# pc_healthypi_move_nRF5340_v1.net
KiCad netlist of a schematic drawn in EAGLE
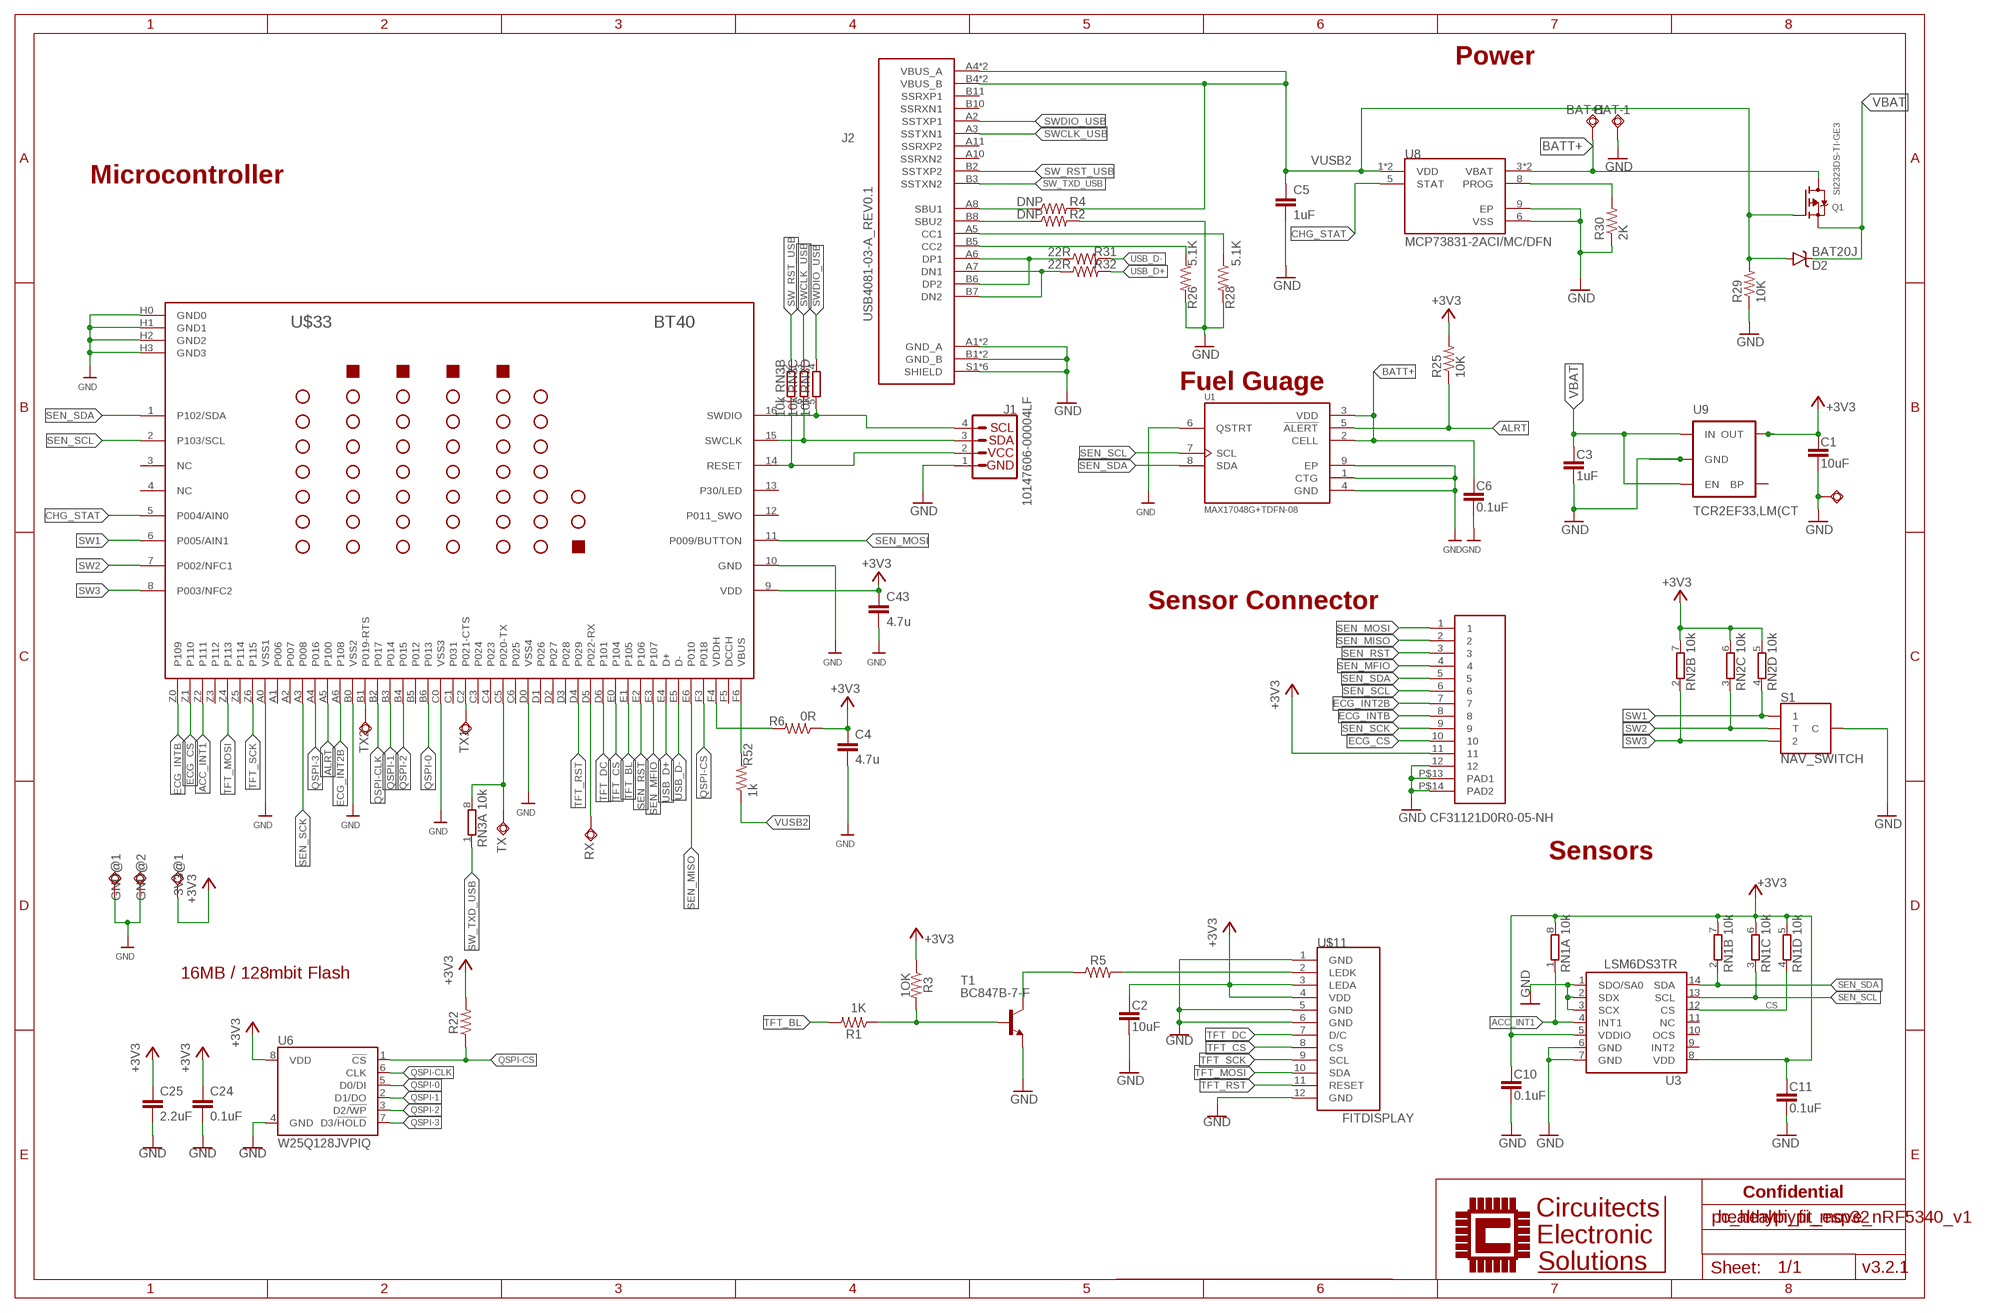
[diagram p0: schematic, sheet 1]

(export (version "E")
  (design (tool "Eeschema 10.0.6"))
  (components
    (comp (ref "3V3@1")
      (value "TPSQTP13SQ")
      (footprint "eagle-import:TP13SQ")
      (libsource (lib "eagle-import") (part "TPSQTP13SQ"))
    )
    (comp (ref "BAT+1")
      (value "TPSQTP13SQ")
      (footprint "eagle-import:TP13SQ")
      (libsource (lib "eagle-import") (part "TPSQTP13SQ"))
    )
    (comp (ref "BAT-1")
      (value "TPSQTP13SQ")
      (footprint "eagle-import:TP13SQ")
      (libsource (lib "eagle-import") (part "TPSQTP13SQ"))
    )
    (comp (ref "C1")
      (value "10uF")
      (footprint "eagle-import:0603@1")
      (libsource (lib "eagle-import") (part "0.1UF-0603-100V-10%"))
    )
    (comp (ref "C2")
      (value "10uF")
      (footprint "eagle-import:0603@1")
      (libsource (lib "eagle-import") (part "0.1UF-0603-100V-10%"))
    )
    (comp (ref "C3")
      (value "1uF")
      (footprint "eagle-import:0402-TIGHT")
      (libsource (lib "eagle-import") (part "0.1UF-0402T-6.3V-10%-X7R"))
    )
    (comp (ref "C4")
      (value "4.7u")
      (footprint "eagle-import:C0402")
      (libsource (lib "eagle-import") (part "C-EUC0402"))
    )
    (comp (ref "C5")
      (value "1uF")
      (footprint "eagle-import:0402-TIGHT")
      (libsource (lib "eagle-import") (part "2.2UF-0402_TIGHT-10V-10%-X5R"))
    )
    (comp (ref "C6")
      (value "0.1uF")
      (footprint "eagle-import:0402-TIGHT")
      (libsource (lib "eagle-import") (part "0.1UF-0402T-6.3V-10%-X7R"))
    )
    (comp (ref "C10")
      (value "0.1uF")
      (footprint "eagle-import:0402-TIGHT")
      (libsource (lib "eagle-import") (part "0.1UF-0402T-6.3V-10%-X7R"))
    )
    (comp (ref "C11")
      (value "0.1uF")
      (footprint "eagle-import:0402-TIGHT")
      (libsource (lib "eagle-import") (part "0.1UF-0402T-6.3V-10%-X7R"))
    )
    (comp (ref "C24")
      (value "0.1uF")
      (footprint "eagle-import:0402-TIGHT")
      (libsource (lib "eagle-import") (part "0.1UF-0402T-6.3V-10%-X7R"))
    )
    (comp (ref "C25")
      (value "2.2uF")
      (footprint "eagle-import:0402-TIGHT")
      (libsource (lib "eagle-import") (part "2.2UF-0402_TIGHT-10V-10%-X5R"))
    )
    (comp (ref "C43")
      (value "4.7u")
      (footprint "eagle-import:C0402")
      (libsource (lib "eagle-import") (part "C-EUC0402"))
    )
    (comp (ref "D2")
      (value "BAT20J")
      (footprint "eagle-import:SOD-323")
      (libsource (lib "eagle-import") (part "DIODE-SCHOTTKY-BAT20J"))
    )
    (comp (ref "GND@1")
      (value "TPSQTP13SQ")
      (footprint "eagle-import:TP13SQ")
      (libsource (lib "eagle-import") (part "TPSQTP13SQ"))
    )
    (comp (ref "GND@2")
      (value "TPSQTP13SQ")
      (footprint "eagle-import:TP13SQ")
      (libsource (lib "eagle-import") (part "TPSQTP13SQ"))
    )
    (comp (ref "J1")
      (value "10147606-00004LF")
      (footprint "eagle-import:JST04_1MM_RA")
      (libsource (lib "eagle-import") (part "QWIIC_CONNECTORJS-1MM"))
    )
    (comp (ref "J2")
      (value "USB4081-03-A_REV0.1")
      (footprint "eagle-import:GCT_USB4081-03-A_REV0.1")
      (fields (field (name "MF") "Global Connector Technology") (field (name "MP") "USB4081-03-A"))
      (libsource (lib "eagle-import") (part "USB4081-03-A_REV0.1"))
    )
    (comp (ref "Q1")
      (value "SI2323DS-TI-GE3")
      (footprint "eagle-import:SOT23-R")
      (libsource (lib "eagle-import") (part "MOSFET-P"))
    )
    (comp (ref "R1")
      (value "200")
      (footprint "eagle-import:R0402")
      (libsource (lib "eagle-import") (part "R-US_R0402"))
    )
    (comp (ref "R2")
      (value "DNP")
      (footprint "eagle-import:0402-RES")
      (libsource (lib "eagle-import") (part "RESISTOR0402-RES"))
    )
    (comp (ref "R3")
      (value "200")
      (footprint "eagle-import:R0402")
      (libsource (lib "eagle-import") (part "R-US_R0402"))
    )
    (comp (ref "R4")
      (value "DNP")
      (footprint "eagle-import:0402-RES")
      (libsource (lib "eagle-import") (part "RESISTOR0402-RES"))
    )
    (comp (ref "R5")
      (value "200R")
      (footprint "eagle-import:R0402")
      (libsource (lib "eagle-import") (part "R-US_R0402"))
    )
    (comp (ref "R6")
      (value "0R")
      (footprint "eagle-import:0402-RES")
      (libsource (lib "eagle-import") (part "RESISTOR0402-RES"))
    )
    (comp (ref "R22")
      (value "10k")
      (footprint "eagle-import:R0402")
      (libsource (lib "eagle-import") (part "R-US_R0402"))
    )
    (comp (ref "R25")
      (value "10K")
      (footprint "eagle-import:0402-RES")
      (libsource (lib "eagle-import") (part "RESISTOR0402-RES"))
    )
    (comp (ref "R26")
      (value "5.1K")
      (footprint "eagle-import:0402-RES")
      (libsource (lib "eagle-import") (part "RESISTOR0402-RES"))
    )
    (comp (ref "R28")
      (value "5.1K")
      (footprint "eagle-import:0402-RES")
      (libsource (lib "eagle-import") (part "RESISTOR0402-RES"))
    )
    (comp (ref "R29")
      (value "10K")
      (footprint "eagle-import:R0402")
      (libsource (lib "eagle-import") (part "R-US_R0402"))
    )
    (comp (ref "R30")
      (value "2K")
      (footprint "eagle-import:R0402")
      (libsource (lib "eagle-import") (part "R-US_R0402"))
    )
    (comp (ref "R31")
      (value "22R")
      (footprint "eagle-import:0402-RES")
      (libsource (lib "eagle-import") (part "RESISTOR0402-RES"))
    )
    (comp (ref "R32")
      (value "22R")
      (footprint "eagle-import:0402-RES")
      (libsource (lib "eagle-import") (part "RESISTOR0402-RES"))
    )
    (comp (ref "R52")
      (value "1k")
      (footprint "eagle-import:0402-RES")
      (libsource (lib "eagle-import") (part "RESISTOR0402-RES"))
    )
    (comp (ref "RN1")
      (value "10k")
      (footprint "eagle-import:4X0402ARV341")
      (libsource (lib "eagle-import") (part "4R-N0402ARV341"))
    )
    (comp (ref "RN2")
      (value "10k")
      (footprint "eagle-import:4X0402ARV341")
      (libsource (lib "eagle-import") (part "4R-N0402ARV341"))
    )
    (comp (ref "RN3")
      (value "10k")
      (footprint "eagle-import:4X0402ARV341")
      (libsource (lib "eagle-import") (part "4R-N0402ARV341"))
    )
    (comp (ref "RX")
      (value "TPSQTP13SQ")
      (footprint "eagle-import:TP13SQ")
      (libsource (lib "eagle-import") (part "TPSQTP13SQ"))
    )
    (comp (ref "S1")
      (value "NAV_SWITCH")
      (footprint "eagle-import:NAV_SWITCH")
      (libsource (lib "eagle-import") (part "NAV_SWITCH"))
    )
    (comp (ref "SWIO6")
      (value "TPSQTP11R")
      (footprint "eagle-import:TP11R")
      (libsource (lib "eagle-import") (part "TPSQTP11R"))
    )
    (comp (ref "T1")
      (value "BC847B-7-F")
      (footprint "eagle-import:SOT23-BEC")
      (libsource (lib "eagle-import") (part "-NPN-SOT23-BECMMBT2222ALT1"))
    )
    (comp (ref "TX")
      (value "TPSQTP13SQ")
      (footprint "eagle-import:TP13SQ")
      (libsource (lib "eagle-import") (part "TPSQTP13SQ"))
    )
    (comp (ref "TX1")
      (value "TPSQTP13SQ")
      (footprint "eagle-import:TP13SQ")
      (libsource (lib "eagle-import") (part "TPSQTP13SQ"))
    )
    (comp (ref "TX2")
      (value "TPSQTP13SQ")
      (footprint "eagle-import:TP13SQ")
      (libsource (lib "eagle-import") (part "TPSQTP13SQ"))
    )
    (comp (ref "U$5")
      (value "CF31121D0R0-05-NH")
      (footprint "eagle-import:CF31121D0R0-05-NH")
      (libsource (lib "eagle-import") (part "CF31121D0R0-05-NH"))
    )
    (comp (ref "U$11")
      (value "FITDISPLAY")
      (footprint "eagle-import:FITDISPLAY")
      (libsource (lib "eagle-import") (part "FITDISPLAY"))
    )
    (comp (ref "U$33")
      (value "BT40")
      (footprint "eagle-import:BT40")
      (libsource (lib "eagle-import") (part "BT40"))
    )
    (comp (ref "U1")
      (value "MAX17048G+TDFN-08")
      (footprint "eagle-import:SON50P200X200X80-9N")
      (fields (field (name "MF") "Analog Devices") (field (name "MP") "MAX17048G+"))
      (libsource (lib "eagle-import") (part "MAX17048G+TDFN-08"))
    )
    (comp (ref "U3")
      (value "LSM6DS3TR")
      (footprint "eagle-import:LGA14L")
      (libsource (lib "eagle-import") (part "LSM6DS3"))
    )
    (comp (ref "U6")
      (value "W25Q128JVPIQ")
      (footprint "eagle-import:WSON-8-6X5-SKINNY_CENTERPAD")
      (libsource (lib "eagle-import") (part "W25QXX128MBIT-6X5-SKINNY_CENTER"))
    )
    (comp (ref "U8")
      (value "MCP73831-2ACI/MC/DFN")
      (footprint "eagle-import:SON50P200X300X100-9N")
      (fields (field (name "MF") "Microchip Technology") (field (name "MP") "MCP73831-2ACI/MC"))
      (libsource (lib "eagle-import") (part "MCP73831-2ACI/MC/DFN"))
    )
    (comp (ref "U9")
      (value "TCR2EF33,LM(CT")
      (footprint "eagle-import:SOT23-5")
      (libsource (lib "eagle-import") (part "V_REG_LDOSMD"))
    )
  )
  (nets
    (net (code "1") (name "+3V3") (class "Default")
      (node (ref "3V3@1") (pin "TP") (pinfunction "TP_TP") (pintype "input"))
      (node (ref "C1") (pin "1") (pinfunction "1_1") (pintype "passive"))
      (node (ref "C10") (pin "1") (pinfunction "1_1") (pintype "passive"))
      (node (ref "C11") (pin "1") (pinfunction "1_1") (pintype "passive"))
      (node (ref "C2") (pin "1") (pinfunction "1_1") (pintype "passive"))
      (node (ref "C24") (pin "1") (pinfunction "1_1") (pintype "passive"))
      (node (ref "C25") (pin "1") (pinfunction "1_1") (pintype "passive"))
      (node (ref "C4") (pin "1") (pinfunction "1_1") (pintype "passive"))
      (node (ref "C43") (pin "1") (pinfunction "1_1") (pintype "passive"))
      (node (ref "R22") (pin "2") (pinfunction "2_2") (pintype "passive"))
      (node (ref "R25") (pin "2") (pinfunction "2_2") (pintype "passive"))
      (node (ref "R3") (pin "1") (pinfunction "1_1") (pintype "passive"))
      (node (ref "R6") (pin "1") (pinfunction "1_1") (pintype "passive"))
      (node (ref "RN1") (pin "5") (pinfunction "2_5") (pintype "passive"))
      (node (ref "RN1") (pin "6") (pinfunction "2_6") (pintype "passive"))
      (node (ref "RN1") (pin "7") (pinfunction "2_7") (pintype "passive"))
      (node (ref "RN1") (pin "8") (pinfunction "2_8") (pintype "passive"))
      (node (ref "RN2") (pin "5") (pinfunction "2_5") (pintype "passive"))
      (node (ref "RN2") (pin "6") (pinfunction "2_6") (pintype "passive"))
      (node (ref "RN2") (pin "7") (pinfunction "2_7") (pintype "passive"))
      (node (ref "U$11") (pin "3") (pinfunction "LEDA_3") (pintype "bidirectional"))
      (node (ref "U$11") (pin "4") (pinfunction "VDD_4") (pintype "bidirectional"))
      (node (ref "U$33") (pin "9") (pinfunction "VDD_9") (pintype "bidirectional"))
      (node (ref "U$5") (pin "11") (pinfunction "11_11") (pintype "bidirectional"))
      (node (ref "U3") (pin "5") (pinfunction "VDDIO_5") (pintype "bidirectional"))
      (node (ref "U3") (pin "8") (pinfunction "VDD_8") (pintype "bidirectional"))
      (node (ref "U6") (pin "8") (pinfunction "VDD_8") (pintype "bidirectional"))
      (node (ref "U9") (pin "5") (pinfunction "OUT_5") (pintype "passive"))
    )
    (net (code "2") (name "/CS") (class "Default")
      (node (ref "RN1") (pin "4") (pinfunction "1_4") (pintype "passive"))
      (node (ref "U3") (pin "12") (pinfunction "CS_12") (pintype "bidirectional"))
    )
    (net (code "3") (name "ACC_INT1") (class "Default")
      (node (ref "RN1") (pin "1") (pinfunction "1_1") (pintype "passive"))
      (node (ref "U$33") (pin "Z2") (pinfunction "P111_Z2") (pintype "bidirectional"))
      (node (ref "U3") (pin "4") (pinfunction "INT1_4") (pintype "bidirectional"))
    )
    (net (code "4") (name "ALRT") (class "Default")
      (node (ref "R25") (pin "1") (pinfunction "1_1") (pintype "passive"))
      (node (ref "U$33") (pin "A5") (pinfunction "P100_A5") (pintype "bidirectional"))
      (node (ref "U1") (pin "5") (pinfunction "~{ALERT}_5") (pintype "output"))
    )
    (net (code "5") (name "BATT+") (class "Default")
      (node (ref "BAT+1") (pin "TP") (pinfunction "TP_TP") (pintype "input"))
      (node (ref "C6") (pin "1") (pinfunction "1_1") (pintype "passive"))
      (node (ref "Q1") (pin "3") (pinfunction "D_3") (pintype "passive"))
      (node (ref "U1") (pin "2") (pinfunction "CELL_2") (pintype "power_in"))
      (node (ref "U1") (pin "3") (pinfunction "VDD_3") (pintype "power_in"))
      (node (ref "U8") (pin "3") (pinfunction "VBAT_3") (pintype "output"))
      (node (ref "U8") (pin "4") (pinfunction "VBAT_4") (pintype "output"))
    )
    (net (code "6") (name "CHG_STAT") (class "Default")
      (node (ref "U$33") (pin "5") (pinfunction "P004/AIN0_5") (pintype "bidirectional"))
      (node (ref "U8") (pin "5") (pinfunction "STAT_5") (pintype "output"))
    )
    (net (code "7") (name "ECG_CS") (class "Default")
      (node (ref "U$33") (pin "Z1") (pinfunction "P110_Z1") (pintype "bidirectional"))
      (node (ref "U$5") (pin "10") (pinfunction "10_10") (pintype "bidirectional"))
    )
    (net (code "8") (name "ECG_INT2B") (class "Default")
      (node (ref "U$33") (pin "A6") (pinfunction "P108_A6") (pintype "bidirectional"))
      (node (ref "U$5") (pin "7") (pinfunction "7_7") (pintype "bidirectional"))
    )
    (net (code "9") (name "ECG_INTB") (class "Default")
      (node (ref "U$33") (pin "Z0") (pinfunction "P109_Z0") (pintype "bidirectional"))
      (node (ref "U$5") (pin "8") (pinfunction "8_8") (pintype "bidirectional"))
    )
    (net (code "10") (name "GND") (class "Default")
      (node (ref "BAT-1") (pin "TP") (pinfunction "TP_TP") (pintype "input"))
      (node (ref "C1") (pin "2") (pinfunction "2_2") (pintype "passive"))
      (node (ref "C10") (pin "2") (pinfunction "2_2") (pintype "passive"))
      (node (ref "C11") (pin "2") (pinfunction "2_2") (pintype "passive"))
      (node (ref "C2") (pin "2") (pinfunction "2_2") (pintype "passive"))
      (node (ref "C24") (pin "2") (pinfunction "2_2") (pintype "passive"))
      (node (ref "C25") (pin "2") (pinfunction "2_2") (pintype "passive"))
      (node (ref "C3") (pin "2") (pinfunction "2_2") (pintype "passive"))
      (node (ref "C4") (pin "2") (pinfunction "2_2") (pintype "passive"))
      (node (ref "C43") (pin "2") (pinfunction "2_2") (pintype "passive"))
      (node (ref "C5") (pin "2") (pinfunction "2_2") (pintype "passive"))
      (node (ref "C6") (pin "2") (pinfunction "2_2") (pintype "passive"))
      (node (ref "GND@1") (pin "TP") (pinfunction "TP_TP") (pintype "input"))
      (node (ref "GND@2") (pin "TP") (pinfunction "TP_TP") (pintype "input"))
      (node (ref "J1") (pin "1") (pinfunction "1_1") (pintype "power_in"))
      (node (ref "J2") (pin "A1") (pinfunction "GND_A_A1") (pintype "power_in"))
      (node (ref "J2") (pin "A12") (pinfunction "GND_A_A12") (pintype "power_in"))
      (node (ref "J2") (pin "B1") (pinfunction "GND_B_B1") (pintype "power_in"))
      (node (ref "J2") (pin "B12") (pinfunction "GND_B_B12") (pintype "power_in"))
      (node (ref "J2") (pin "S1") (pinfunction "SHIELD_S1") (pintype "passive"))
      (node (ref "J2") (pin "S2") (pinfunction "SHIELD_S2") (pintype "passive"))
      (node (ref "J2") (pin "S3") (pinfunction "SHIELD_S3") (pintype "passive"))
      (node (ref "J2") (pin "S4") (pinfunction "SHIELD_S4") (pintype "passive"))
      (node (ref "J2") (pin "S5") (pinfunction "SHIELD_S5") (pintype "passive"))
      (node (ref "J2") (pin "S6") (pinfunction "SHIELD_S6") (pintype "passive"))
      (node (ref "R2") (pin "2") (pinfunction "2_2") (pintype "passive"))
      (node (ref "R26") (pin "2") (pinfunction "2_2") (pintype "passive"))
      (node (ref "R28") (pin "2") (pinfunction "2_2") (pintype "passive"))
      (node (ref "R29") (pin "1") (pinfunction "1_1") (pintype "passive"))
      (node (ref "R30") (pin "1") (pinfunction "1_1") (pintype "passive"))
      (node (ref "S1") (pin "C") (pinfunction "C_C") (pintype "power_in"))
      (node (ref "SWIO6") (pin "TP") (pinfunction "TP_TP") (pintype "input"))
      (node (ref "T1") (pin "E") (pinfunction "E_E") (pintype "passive"))
      (node (ref "U$11") (pin "1") (pinfunction "GND_1") (pintype "bidirectional"))
      (node (ref "U$11") (pin "12") (pinfunction "GND_12") (pintype "bidirectional"))
      (node (ref "U$11") (pin "5") (pinfunction "GND_5") (pintype "bidirectional"))
      (node (ref "U$11") (pin "6") (pinfunction "GND_6") (pintype "bidirectional"))
      (node (ref "U$33") (pin "10") (pinfunction "GND_10") (pintype "bidirectional"))
      (node (ref "U$33") (pin "A0") (pinfunction "VSS1_A0") (pintype "bidirectional"))
      (node (ref "U$33") (pin "B0") (pinfunction "VSS2_B0") (pintype "bidirectional"))
      (node (ref "U$33") (pin "C0") (pinfunction "VSS3_C0") (pintype "bidirectional"))
      (node (ref "U$33") (pin "D0") (pinfunction "VSS4_D0") (pintype "bidirectional"))
      (node (ref "U$33") (pin "H0") (pinfunction "GND0_H0") (pintype "bidirectional"))
      (node (ref "U$33") (pin "H1") (pinfunction "GND1_H1") (pintype "bidirectional"))
      (node (ref "U$33") (pin "H2") (pinfunction "GND2_H2") (pintype "bidirectional"))
      (node (ref "U$33") (pin "H3") (pinfunction "GND3_H3") (pintype "bidirectional"))
      (node (ref "U$5") (pin "12") (pinfunction "12_12") (pintype "bidirectional"))
      (node (ref "U$5") (pin "P$13") (pinfunction "PAD1_P$13") (pintype "bidirectional"))
      (node (ref "U$5") (pin "P$14") (pinfunction "PAD2_P$14") (pintype "bidirectional"))
      (node (ref "U1") (pin "1") (pinfunction "CTG_1") (pintype "power_in"))
      (node (ref "U1") (pin "4") (pinfunction "GND_4") (pintype "power_in"))
      (node (ref "U1") (pin "6") (pinfunction "QSTRT_6") (pintype "input"))
      (node (ref "U1") (pin "9") (pinfunction "EP_9") (pintype "power_in"))
      (node (ref "U3") (pin "1") (pinfunction "SDO/SA0_1") (pintype "bidirectional"))
      (node (ref "U3") (pin "2") (pinfunction "SDX_2") (pintype "bidirectional"))
      (node (ref "U3") (pin "3") (pinfunction "SCX_3") (pintype "bidirectional"))
      (node (ref "U3") (pin "6") (pinfunction "GND_6") (pintype "bidirectional"))
      (node (ref "U3") (pin "7") (pinfunction "GND_7") (pintype "bidirectional"))
      (node (ref "U6") (pin "4") (pinfunction "GND_4") (pintype "bidirectional"))
      (node (ref "U8") (pin "6") (pinfunction "VSS_6") (pintype "power_in"))
      (node (ref "U8") (pin "9") (pinfunction "EP_9") (pintype "power_in"))
      (node (ref "U9") (pin "2") (pinfunction "GND_2") (pintype "input"))
    )
    (net (code "11") (name "Net-(J2-CC1)") (class "Default")
      (node (ref "J2") (pin "A5") (pinfunction "CC1_A5") (pintype "bidirectional"))
      (node (ref "R28") (pin "1") (pinfunction "1_1") (pintype "passive"))
    )
    (net (code "12") (name "Net-(J2-CC2)") (class "Default")
      (node (ref "J2") (pin "B5") (pinfunction "CC2_B5") (pintype "bidirectional"))
      (node (ref "R26") (pin "1") (pinfunction "1_1") (pintype "passive"))
    )
    (net (code "13") (name "Net-(J2-DN1)") (class "Default")
      (node (ref "J2") (pin "A7") (pinfunction "DN1_A7") (pintype "bidirectional"))
      (node (ref "J2") (pin "B7") (pinfunction "DN2_B7") (pintype "bidirectional"))
      (node (ref "R32") (pin "1") (pinfunction "1_1") (pintype "passive"))
    )
    (net (code "14") (name "Net-(J2-DP1)") (class "Default")
      (node (ref "J2") (pin "A6") (pinfunction "DP1_A6") (pintype "bidirectional"))
      (node (ref "J2") (pin "B6") (pinfunction "DP2_B6") (pintype "bidirectional"))
      (node (ref "R31") (pin "1") (pinfunction "1_1") (pintype "passive"))
    )
    (net (code "15") (name "Net-(J2-SBU1)") (class "Default")
      (node (ref "J2") (pin "A8") (pinfunction "SBU1_A8") (pintype "bidirectional"))
      (node (ref "R4") (pin "1") (pinfunction "1_1") (pintype "passive"))
    )
    (net (code "16") (name "Net-(J2-SBU2)") (class "Default")
      (node (ref "J2") (pin "B8") (pinfunction "SBU2_B8") (pintype "bidirectional"))
      (node (ref "R2") (pin "1") (pinfunction "1_1") (pintype "passive"))
    )
    (net (code "17") (name "Net-(R1-Pad1)") (class "Default")
      (node (ref "R1") (pin "1") (pinfunction "1_1") (pintype "passive"))
      (node (ref "R3") (pin "2") (pinfunction "2_2") (pintype "passive"))
      (node (ref "T1") (pin "B") (pinfunction "B_B") (pintype "passive"))
    )
    (net (code "18") (name "Net-(R5-Pad1)") (class "Default")
      (node (ref "R5") (pin "1") (pinfunction "1_1") (pintype "passive"))
      (node (ref "T1") (pin "C") (pinfunction "C_C") (pintype "passive"))
    )
    (net (code "19") (name "Net-(RN3A-2)") (class "Default")
      (node (ref "RN3") (pin "8") (pinfunction "2_8") (pintype "passive"))
      (node (ref "TX") (pin "TP") (pinfunction "TP_TP") (pintype "input"))
      (node (ref "U$33") (pin "C5") (pinfunction "P020-TX_C5") (pintype "bidirectional"))
    )
    (net (code "20") (name "Net-(RN3B-2)") (class "Default")
      (node (ref "J1") (pin "2") (pinfunction "2_2") (pintype "power_in"))
      (node (ref "RN3") (pin "7") (pinfunction "2_7") (pintype "passive"))
      (node (ref "U$33") (pin "14") (pinfunction "RESET_14") (pintype "bidirectional"))
    )
    (net (code "21") (name "Net-(RN3C-2)") (class "Default")
      (node (ref "J1") (pin "3") (pinfunction "3_3") (pintype "passive"))
      (node (ref "RN3") (pin "6") (pinfunction "2_6") (pintype "passive"))
      (node (ref "U$33") (pin "15") (pinfunction "SWCLK_15") (pintype "bidirectional"))
    )
    (net (code "22") (name "Net-(RN3D-2)") (class "Default")
      (node (ref "J1") (pin "4") (pinfunction "4_4") (pintype "passive"))
      (node (ref "RN3") (pin "5") (pinfunction "2_5") (pintype "passive"))
      (node (ref "U$33") (pin "16") (pinfunction "SWDIO_16") (pintype "bidirectional"))
    )
    (net (code "23") (name "Net-(U$11-LEDK)") (class "Default")
      (node (ref "R5") (pin "2") (pinfunction "2_2") (pintype "passive"))
      (node (ref "U$11") (pin "2") (pinfunction "LEDK_2") (pintype "bidirectional"))
    )
    (net (code "24") (name "Net-(U$33-P019-RTS)") (class "Default")
      (node (ref "TX2") (pin "TP") (pinfunction "TP_TP") (pintype "input"))
      (node (ref "U$33") (pin "B1") (pinfunction "P019-RTS_B1") (pintype "bidirectional"))
    )
    (net (code "25") (name "Net-(U$33-P021-CTS)") (class "Default")
      (node (ref "TX1") (pin "TP") (pinfunction "TP_TP") (pintype "input"))
      (node (ref "U$33") (pin "C2") (pinfunction "P021-CTS_C2") (pintype "bidirectional"))
    )
    (net (code "26") (name "Net-(U$33-P022-RX)") (class "Default")
      (node (ref "RX") (pin "TP") (pinfunction "TP_TP") (pintype "input"))
      (node (ref "U$33") (pin "D5") (pinfunction "P022-RX_D5") (pintype "bidirectional"))
    )
    (net (code "27") (name "Net-(U$33-VBUS)") (class "Default")
      (node (ref "R52") (pin "2") (pinfunction "2_2") (pintype "passive"))
      (node (ref "U$33") (pin "F6") (pinfunction "VBUS_F6") (pintype "bidirectional"))
    )
    (net (code "28") (name "Net-(U$33-VDDH)") (class "Default")
      (node (ref "R6") (pin "2") (pinfunction "2_2") (pintype "passive"))
      (node (ref "U$33") (pin "F4") (pinfunction "VDDH_F4") (pintype "bidirectional"))
    )
    (net (code "29") (name "Net-(U8-PROG)") (class "Default")
      (node (ref "R30") (pin "2") (pinfunction "2_2") (pintype "passive"))
      (node (ref "U8") (pin "8") (pinfunction "PROG_8") (pintype "input"))
    )
    (net (code "30") (name "QSPI-0") (class "Default")
      (node (ref "U$33") (pin "B6") (pinfunction "P013_B6") (pintype "bidirectional"))
      (node (ref "U6") (pin "5") (pinfunction "D0/DI_5") (pintype "bidirectional"))
    )
    (net (code "31") (name "QSPI-1") (class "Default")
      (node (ref "U$33") (pin "B3") (pinfunction "P014_B3") (pintype "bidirectional"))
      (node (ref "U6") (pin "2") (pinfunction "D1/DO_2") (pintype "bidirectional"))
    )
    (net (code "32") (name "QSPI-2") (class "Default")
      (node (ref "U$33") (pin "B4") (pinfunction "P015_B4") (pintype "bidirectional"))
      (node (ref "U6") (pin "3") (pinfunction "D2/~{WP}_3") (pintype "bidirectional"))
    )
    (net (code "33") (name "QSPI-3") (class "Default")
      (node (ref "U$33") (pin "A4") (pinfunction "P016_A4") (pintype "bidirectional"))
      (node (ref "U6") (pin "7") (pinfunction "D3/~{HOLD}_7") (pintype "bidirectional"))
    )
    (net (code "34") (name "QSPI-CLK") (class "Default")
      (node (ref "U$33") (pin "B2") (pinfunction "P017_B2") (pintype "bidirectional"))
      (node (ref "U6") (pin "6") (pinfunction "CLK_6") (pintype "bidirectional"))
    )
    (net (code "35") (name "QSPI-CS") (class "Default")
      (node (ref "R22") (pin "1") (pinfunction "1_1") (pintype "passive"))
      (node (ref "U$33") (pin "F3") (pinfunction "P018_F3") (pintype "bidirectional"))
      (node (ref "U6") (pin "1") (pinfunction "~{CS}_1") (pintype "bidirectional"))
    )
    (net (code "36") (name "SEN_MFIO") (class "Default")
      (node (ref "U$33") (pin "E3") (pinfunction "P107_E3") (pintype "bidirectional"))
      (node (ref "U$5") (pin "4") (pinfunction "4_4") (pintype "bidirectional"))
    )
    (net (code "37") (name "SEN_MISO") (class "Default")
      (node (ref "U$33") (pin "E6") (pinfunction "P010_E6") (pintype "bidirectional"))
      (node (ref "U$5") (pin "2") (pinfunction "2_2") (pintype "bidirectional"))
    )
    (net (code "38") (name "SEN_MOSI") (class "Default")
      (node (ref "U$33") (pin "11") (pinfunction "P009/BUTTON_11") (pintype "bidirectional"))
      (node (ref "U$5") (pin "1") (pinfunction "1_1") (pintype "bidirectional"))
    )
    (net (code "39") (name "SEN_RST") (class "Default")
      (node (ref "U$33") (pin "E2") (pinfunction "P106_E2") (pintype "bidirectional"))
      (node (ref "U$5") (pin "3") (pinfunction "3_3") (pintype "bidirectional"))
    )
    (net (code "40") (name "SEN_SCK") (class "Default")
      (node (ref "U$33") (pin "A3") (pinfunction "P008_A3") (pintype "bidirectional"))
      (node (ref "U$5") (pin "9") (pinfunction "9_9") (pintype "bidirectional"))
    )
    (net (code "41") (name "SEN_SCL") (class "Default")
      (node (ref "RN1") (pin "3") (pinfunction "1_3") (pintype "passive"))
      (node (ref "U$33") (pin "2") (pinfunction "P103/SCL_2") (pintype "bidirectional"))
      (node (ref "U$5") (pin "6") (pinfunction "6_6") (pintype "bidirectional"))
      (node (ref "U1") (pin "7") (pinfunction "SCL_7") (pintype "input"))
      (node (ref "U3") (pin "13") (pinfunction "SCL_13") (pintype "bidirectional"))
    )
    (net (code "42") (name "SEN_SDA") (class "Default")
      (node (ref "RN1") (pin "2") (pinfunction "1_2") (pintype "passive"))
      (node (ref "U$33") (pin "1") (pinfunction "P102/SDA_1") (pintype "bidirectional"))
      (node (ref "U$5") (pin "5") (pinfunction "5_5") (pintype "bidirectional"))
      (node (ref "U1") (pin "8") (pinfunction "SDA_8") (pintype "bidirectional"))
      (node (ref "U3") (pin "14") (pinfunction "SDA_14") (pintype "bidirectional"))
    )
    (net (code "43") (name "SW1") (class "Default")
      (node (ref "RN2") (pin "4") (pinfunction "1_4") (pintype "passive"))
      (node (ref "S1") (pin "1") (pinfunction "1_1") (pintype "input"))
      (node (ref "U$33") (pin "6") (pinfunction "P005/AIN1_6") (pintype "bidirectional"))
    )
    (net (code "44") (name "SW2") (class "Default")
      (node (ref "RN2") (pin "3") (pinfunction "1_3") (pintype "passive"))
      (node (ref "S1") (pin "T") (pinfunction "T_T") (pintype "input"))
      (node (ref "U$33") (pin "7") (pinfunction "P002/NFC1_7") (pintype "bidirectional"))
    )
    (net (code "45") (name "SW3") (class "Default")
      (node (ref "RN2") (pin "2") (pinfunction "1_2") (pintype "passive"))
      (node (ref "S1") (pin "2") (pinfunction "2_2") (pintype "input"))
      (node (ref "U$33") (pin "8") (pinfunction "P003/NFC2_8") (pintype "bidirectional"))
    )
    (net (code "46") (name "SWCLK_USB") (class "Default")
      (node (ref "J2") (pin "A3") (pinfunction "SSTXN1_A3") (pintype "bidirectional"))
      (node (ref "RN3") (pin "3") (pinfunction "1_3") (pintype "passive"))
    )
    (net (code "47") (name "SWDIO_USB") (class "Default")
      (node (ref "J2") (pin "A2") (pinfunction "SSTXP1_A2") (pintype "bidirectional"))
      (node (ref "RN3") (pin "4") (pinfunction "1_4") (pintype "passive"))
    )
    (net (code "48") (name "SW_RST_USB") (class "Default")
      (node (ref "J2") (pin "B2") (pinfunction "SSTXP2_B2") (pintype "bidirectional"))
      (node (ref "RN3") (pin "2") (pinfunction "1_2") (pintype "passive"))
    )
    (net (code "49") (name "SW_TXD_USB") (class "Default")
      (node (ref "J2") (pin "B3") (pinfunction "SSTXN2_B3") (pintype "bidirectional"))
      (node (ref "RN3") (pin "1") (pinfunction "1_1") (pintype "passive"))
    )
    (net (code "50") (name "TFT_BL") (class "Default")
      (node (ref "R1") (pin "2") (pinfunction "2_2") (pintype "passive"))
      (node (ref "U$33") (pin "E1") (pinfunction "P105_E1") (pintype "bidirectional"))
    )
    (net (code "51") (name "TFT_CS") (class "Default")
      (node (ref "U$11") (pin "8") (pinfunction "CS_8") (pintype "bidirectional"))
      (node (ref "U$33") (pin "E0") (pinfunction "P104_E0") (pintype "bidirectional"))
    )
    (net (code "52") (name "TFT_DC") (class "Default")
      (node (ref "U$11") (pin "7") (pinfunction "D/C_7") (pintype "bidirectional"))
      (node (ref "U$33") (pin "D6") (pinfunction "P101_D6") (pintype "bidirectional"))
    )
    (net (code "53") (name "TFT_MOSI") (class "Default")
      (node (ref "U$11") (pin "10") (pinfunction "SDA_10") (pintype "bidirectional"))
      (node (ref "U$33") (pin "Z4") (pinfunction "P113_Z4") (pintype "bidirectional"))
    )
    (net (code "54") (name "TFT_RST") (class "Default")
      (node (ref "U$11") (pin "11") (pinfunction "RESET_11") (pintype "bidirectional"))
      (node (ref "U$33") (pin "D4") (pinfunction "P029_D4") (pintype "bidirectional"))
    )
    (net (code "55") (name "TFT_SCK") (class "Default")
      (node (ref "U$11") (pin "9") (pinfunction "SCL_9") (pintype "bidirectional"))
      (node (ref "U$33") (pin "Z6") (pinfunction "P115_Z6") (pintype "bidirectional"))
    )
    (net (code "56") (name "USB_D+") (class "Default")
      (node (ref "R32") (pin "2") (pinfunction "2_2") (pintype "passive"))
      (node (ref "U$33") (pin "E4") (pinfunction "D+_E4") (pintype "bidirectional"))
    )
    (net (code "57") (name "USB_D-") (class "Default")
      (node (ref "R31") (pin "2") (pinfunction "2_2") (pintype "passive"))
      (node (ref "U$33") (pin "E5") (pinfunction "D-_E5") (pintype "bidirectional"))
    )
    (net (code "58") (name "VBAT") (class "Default")
      (node (ref "C3") (pin "1") (pinfunction "1_1") (pintype "passive"))
      (node (ref "D2") (pin "C") (pinfunction "C_C") (pintype "passive"))
      (node (ref "Q1") (pin "2") (pinfunction "S_2") (pintype "passive"))
      (node (ref "U9") (pin "1") (pinfunction "IN_1") (pintype "input"))
      (node (ref "U9") (pin "3") (pinfunction "EN_3") (pintype "input"))
    )
    (net (code "59") (name "VUSB2") (class "Default")
      (node (ref "C5") (pin "1") (pinfunction "1_1") (pintype "passive"))
      (node (ref "D2") (pin "A") (pinfunction "A_A") (pintype "passive"))
      (node (ref "J2") (pin "A4") (pinfunction "VBUS_A_A4") (pintype "power_in"))
      (node (ref "J2") (pin "A9") (pinfunction "VBUS_A_A9") (pintype "power_in"))
      (node (ref "J2") (pin "B4") (pinfunction "VBUS_B_B4") (pintype "power_in"))
      (node (ref "J2") (pin "B9") (pinfunction "VBUS_B_B9") (pintype "power_in"))
      (node (ref "Q1") (pin "1") (pinfunction "G_1") (pintype "passive"))
      (node (ref "R29") (pin "2") (pinfunction "2_2") (pintype "passive"))
      (node (ref "R4") (pin "2") (pinfunction "2_2") (pintype "passive"))
      (node (ref "R52") (pin "1") (pinfunction "1_1") (pintype "passive"))
      (node (ref "U8") (pin "1") (pinfunction "VDD_1") (pintype "power_in"))
      (node (ref "U8") (pin "2") (pinfunction "VDD_2") (pintype "power_in"))
    )
    (net (code "60") (name "unconnected-(J2-SSRXN1-PadB10)") (class "Default")
      (node (ref "J2") (pin "B10") (pinfunction "SSRXN1_B10") (pintype "bidirectional"))
    )
    (net (code "61") (name "unconnected-(J2-SSRXN2-PadA10)") (class "Default")
      (node (ref "J2") (pin "A10") (pinfunction "SSRXN2_A10") (pintype "bidirectional"))
    )
    (net (code "62") (name "unconnected-(J2-SSRXP1-PadB11)") (class "Default")
      (node (ref "J2") (pin "B11") (pinfunction "SSRXP1_B11") (pintype "bidirectional"))
    )
    (net (code "63") (name "unconnected-(J2-SSRXP2-PadA11)") (class "Default")
      (node (ref "J2") (pin "A11") (pinfunction "SSRXP2_A11") (pintype "bidirectional"))
    )
    (net (code "64") (name "unconnected-(U$33-DCCH-PadF5)") (class "Default")
      (node (ref "U$33") (pin "F5") (pinfunction "DCCH_F5") (pintype "bidirectional"))
    )
    (net (code "65") (name "unconnected-(U$33-NC-Pad3)") (class "Default")
      (node (ref "U$33") (pin "3") (pinfunction "NC_3") (pintype "bidirectional"))
    )
    (net (code "66") (name "unconnected-(U$33-NC-Pad4)") (class "Default")
      (node (ref "U$33") (pin "4") (pinfunction "NC_4") (pintype "bidirectional"))
    )
    (net (code "67") (name "unconnected-(U$33-P006-PadA1)") (class "Default")
      (node (ref "U$33") (pin "A1") (pinfunction "P006_A1") (pintype "bidirectional"))
    )
    (net (code "68") (name "unconnected-(U$33-P007-PadA2)") (class "Default")
      (node (ref "U$33") (pin "A2") (pinfunction "P007_A2") (pintype "bidirectional"))
    )
    (net (code "69") (name "unconnected-(U$33-P011_SWO-Pad12)") (class "Default")
      (node (ref "U$33") (pin "12") (pinfunction "P011_SWO_12") (pintype "bidirectional"))
    )
    (net (code "70") (name "unconnected-(U$33-P012-PadB5)") (class "Default")
      (node (ref "U$33") (pin "B5") (pinfunction "P012_B5") (pintype "bidirectional"))
    )
    (net (code "71") (name "unconnected-(U$33-P023-PadC4)") (class "Default")
      (node (ref "U$33") (pin "C4") (pinfunction "P023_C4") (pintype "bidirectional"))
    )
    (net (code "72") (name "unconnected-(U$33-P024-PadC3)") (class "Default")
      (node (ref "U$33") (pin "C3") (pinfunction "P024_C3") (pintype "bidirectional"))
    )
    (net (code "73") (name "unconnected-(U$33-P025-PadC6)") (class "Default")
      (node (ref "U$33") (pin "C6") (pinfunction "P025_C6") (pintype "bidirectional"))
    )
    (net (code "74") (name "unconnected-(U$33-P026-PadD1)") (class "Default")
      (node (ref "U$33") (pin "D1") (pinfunction "P026_D1") (pintype "bidirectional"))
    )
    (net (code "75") (name "unconnected-(U$33-P027-PadD2)") (class "Default")
      (node (ref "U$33") (pin "D2") (pinfunction "P027_D2") (pintype "bidirectional"))
    )
    (net (code "76") (name "unconnected-(U$33-P028-PadD3)") (class "Default")
      (node (ref "U$33") (pin "D3") (pinfunction "P028_D3") (pintype "bidirectional"))
    )
    (net (code "77") (name "unconnected-(U$33-P30{slash}LED-Pad13)") (class "Default")
      (node (ref "U$33") (pin "13") (pinfunction "P30/LED_13") (pintype "bidirectional"))
    )
    (net (code "78") (name "unconnected-(U$33-P031-PadC1)") (class "Default")
      (node (ref "U$33") (pin "C1") (pinfunction "P031_C1") (pintype "bidirectional"))
    )
    (net (code "79") (name "unconnected-(U$33-P112-PadZ3)") (class "Default")
      (node (ref "U$33") (pin "Z3") (pinfunction "P112_Z3") (pintype "bidirectional"))
    )
    (net (code "80") (name "unconnected-(U$33-P114-PadZ5)") (class "Default")
      (node (ref "U$33") (pin "Z5") (pinfunction "P114_Z5") (pintype "bidirectional"))
    )
    (net (code "81") (name "unconnected-(U3-INT2-Pad9)") (class "Default")
      (node (ref "U3") (pin "9") (pinfunction "INT2_9") (pintype "bidirectional"))
    )
    (net (code "82") (name "unconnected-(U3-NC-Pad11)") (class "Default")
      (node (ref "U3") (pin "11") (pinfunction "NC_11") (pintype "bidirectional"))
    )
    (net (code "83") (name "unconnected-(U3-OCS-Pad10)") (class "Default")
      (node (ref "U3") (pin "10") (pinfunction "OCS_10") (pintype "bidirectional"))
    )
    (net (code "84") (name "unconnected-(U9-BP-Pad4)") (class "Default")
      (node (ref "U9") (pin "4") (pinfunction "BP_4") (pintype "input"))
    )
  )
)
